# DRV8825_SHIELD_V2.net
KiCad netlist of a schematic drawn in EAGLE
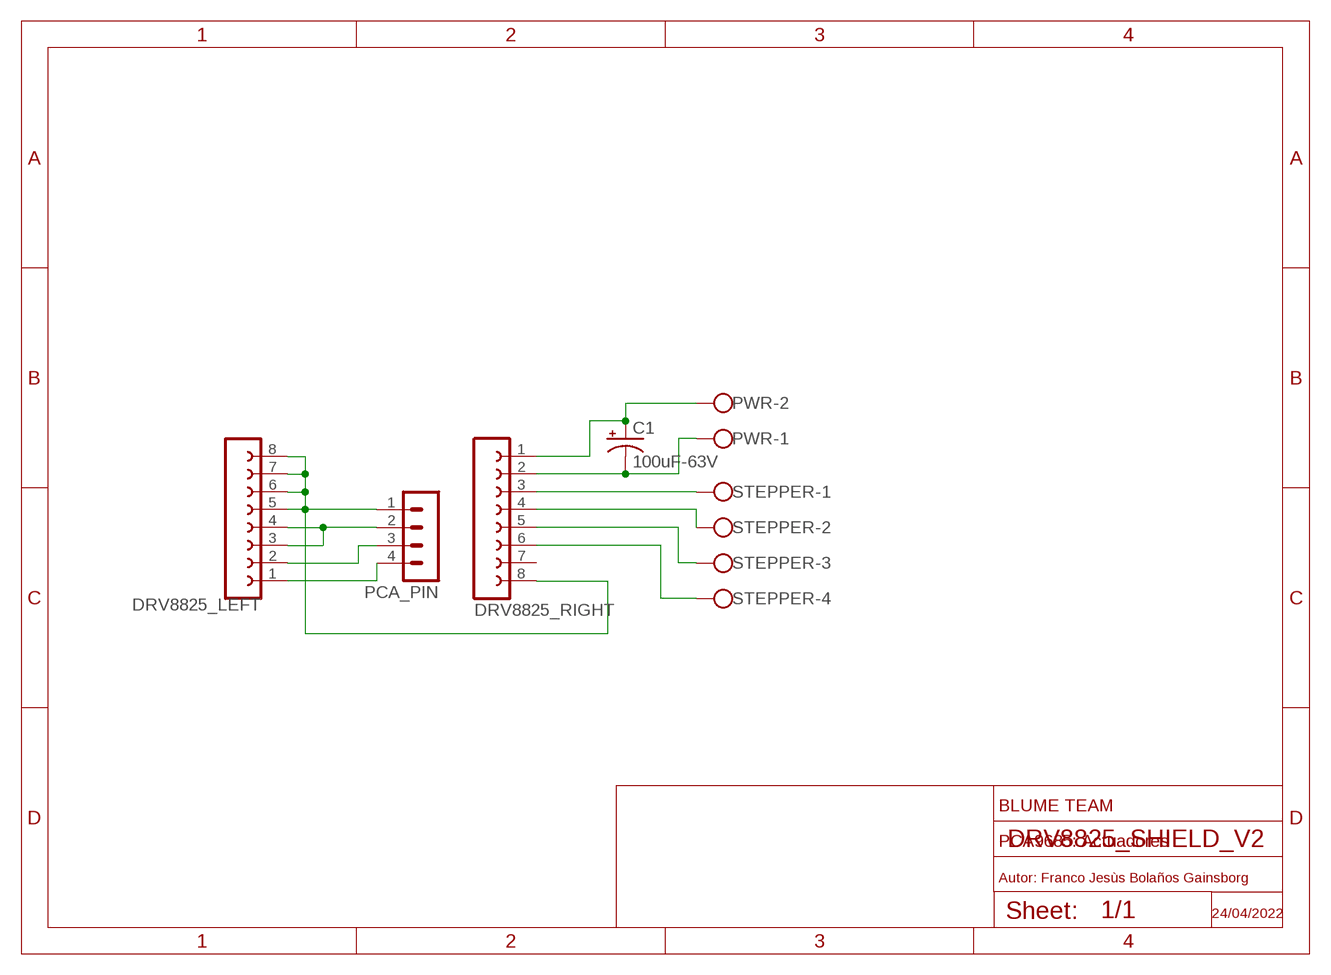
[diagram p0: schematic, sheet 1]

(export (version "E")
  (design (tool "Eeschema 10.0.6"))
  (components
    (comp (ref "C1")
      (value "100uF-63V")
      (footprint "eagle-import:E5-10,5")
      (libsource (lib "eagle-import") (part "CPOL-USE5-10.5"))
    )
    (comp (ref "DRV8825_LEFT")
      (value "FE08-1")
      (footprint "eagle-import:FE08")
      (libsource (lib "eagle-import") (part "FE08-1"))
    )
    (comp (ref "DRV8825_RIGHT")
      (value "FE08-1")
      (footprint "eagle-import:FE08")
      (libsource (lib "eagle-import") (part "FE08-1"))
    )
    (comp (ref "PCA_PIN")
      (value "MA04-1")
      (footprint "eagle-import:MA04-1")
      (libsource (lib "eagle-import") (part "MA04-1"))
    )
    (comp (ref "PWR")
      (value "W237-102")
      (footprint "eagle-import:W237-102")
      (fields (field (name "MPN") "237-102"))
      (libsource (lib "eagle-import") (part "W237-102"))
    )
    (comp (ref "STEPPER")
      (value "W237-4")
      (footprint "eagle-import:W237-4")
      (libsource (lib "eagle-import") (part "W237-4"))
    )
  )
  (nets
    (net (code "1") (name "Net-(DRV8825_LEFT-Pad1)") (class "Default")
      (node (ref "DRV8825_LEFT") (pin "1") (pinfunction "1_1") (pintype "passive"))
      (node (ref "PCA_PIN") (pin "4") (pinfunction "4_4") (pintype "passive"))
    )
    (net (code "2") (name "Net-(DRV8825_LEFT-Pad2)") (class "Default")
      (node (ref "DRV8825_LEFT") (pin "2") (pinfunction "2_2") (pintype "passive"))
      (node (ref "PCA_PIN") (pin "3") (pinfunction "3_3") (pintype "passive"))
    )
    (net (code "3") (name "Net-(DRV8825_LEFT-Pad3)") (class "Default")
      (node (ref "DRV8825_LEFT") (pin "3") (pinfunction "3_3") (pintype "passive"))
      (node (ref "DRV8825_LEFT") (pin "4") (pinfunction "4_4") (pintype "passive"))
      (node (ref "PCA_PIN") (pin "2") (pinfunction "2_2") (pintype "passive"))
    )
    (net (code "4") (name "Net-(DRV8825_LEFT-Pad5)") (class "Default")
      (node (ref "DRV8825_LEFT") (pin "5") (pinfunction "5_5") (pintype "passive"))
      (node (ref "DRV8825_LEFT") (pin "6") (pinfunction "6_6") (pintype "passive"))
      (node (ref "DRV8825_LEFT") (pin "7") (pinfunction "7_7") (pintype "passive"))
      (node (ref "DRV8825_LEFT") (pin "8") (pinfunction "8_8") (pintype "passive"))
      (node (ref "DRV8825_RIGHT") (pin "8") (pinfunction "8_8") (pintype "passive"))
      (node (ref "PCA_PIN") (pin "1") (pinfunction "1_1") (pintype "passive"))
    )
    (net (code "5") (name "Net-(PWRA-KL)") (class "Default")
      (node (ref "C1") (pin "-") (pinfunction "-_-") (pintype "passive"))
      (node (ref "DRV8825_RIGHT") (pin "2") (pinfunction "2_2") (pintype "passive"))
      (node (ref "PWR") (pin "1") (pinfunction "KL_1") (pintype "passive"))
    )
    (net (code "6") (name "Net-(PWRB-KL)") (class "Default")
      (node (ref "C1") (pin "+") (pinfunction "+_+") (pintype "passive"))
      (node (ref "DRV8825_RIGHT") (pin "1") (pinfunction "1_1") (pintype "passive"))
      (node (ref "PWR") (pin "2") (pinfunction "KL_2") (pintype "passive"))
    )
    (net (code "7") (name "Net-(STEPPERA-KL)") (class "Default")
      (node (ref "DRV8825_RIGHT") (pin "3") (pinfunction "3_3") (pintype "passive"))
      (node (ref "STEPPER") (pin "1") (pinfunction "KL_1") (pintype "passive"))
    )
    (net (code "8") (name "Net-(STEPPERB-KL)") (class "Default")
      (node (ref "DRV8825_RIGHT") (pin "4") (pinfunction "4_4") (pintype "passive"))
      (node (ref "STEPPER") (pin "2") (pinfunction "KL_2") (pintype "passive"))
    )
    (net (code "9") (name "Net-(STEPPERC-KL)") (class "Default")
      (node (ref "DRV8825_RIGHT") (pin "5") (pinfunction "5_5") (pintype "passive"))
      (node (ref "STEPPER") (pin "3") (pinfunction "KL_3") (pintype "passive"))
    )
    (net (code "10") (name "Net-(STEPPERD-KL)") (class "Default")
      (node (ref "DRV8825_RIGHT") (pin "6") (pinfunction "6_6") (pintype "passive"))
      (node (ref "STEPPER") (pin "4") (pinfunction "KL_4") (pintype "passive"))
    )
    (net (code "11") (name "unconnected-(DRV8825_RIGHT-Pad7)") (class "Default")
      (node (ref "DRV8825_RIGHT") (pin "7") (pinfunction "7_7") (pintype "passive"))
    )
  )
)
